# SCH_PCEngineExpansionConnector_2024-10-2.net
KiCad netlist of a schematic drawn in EasyEDA
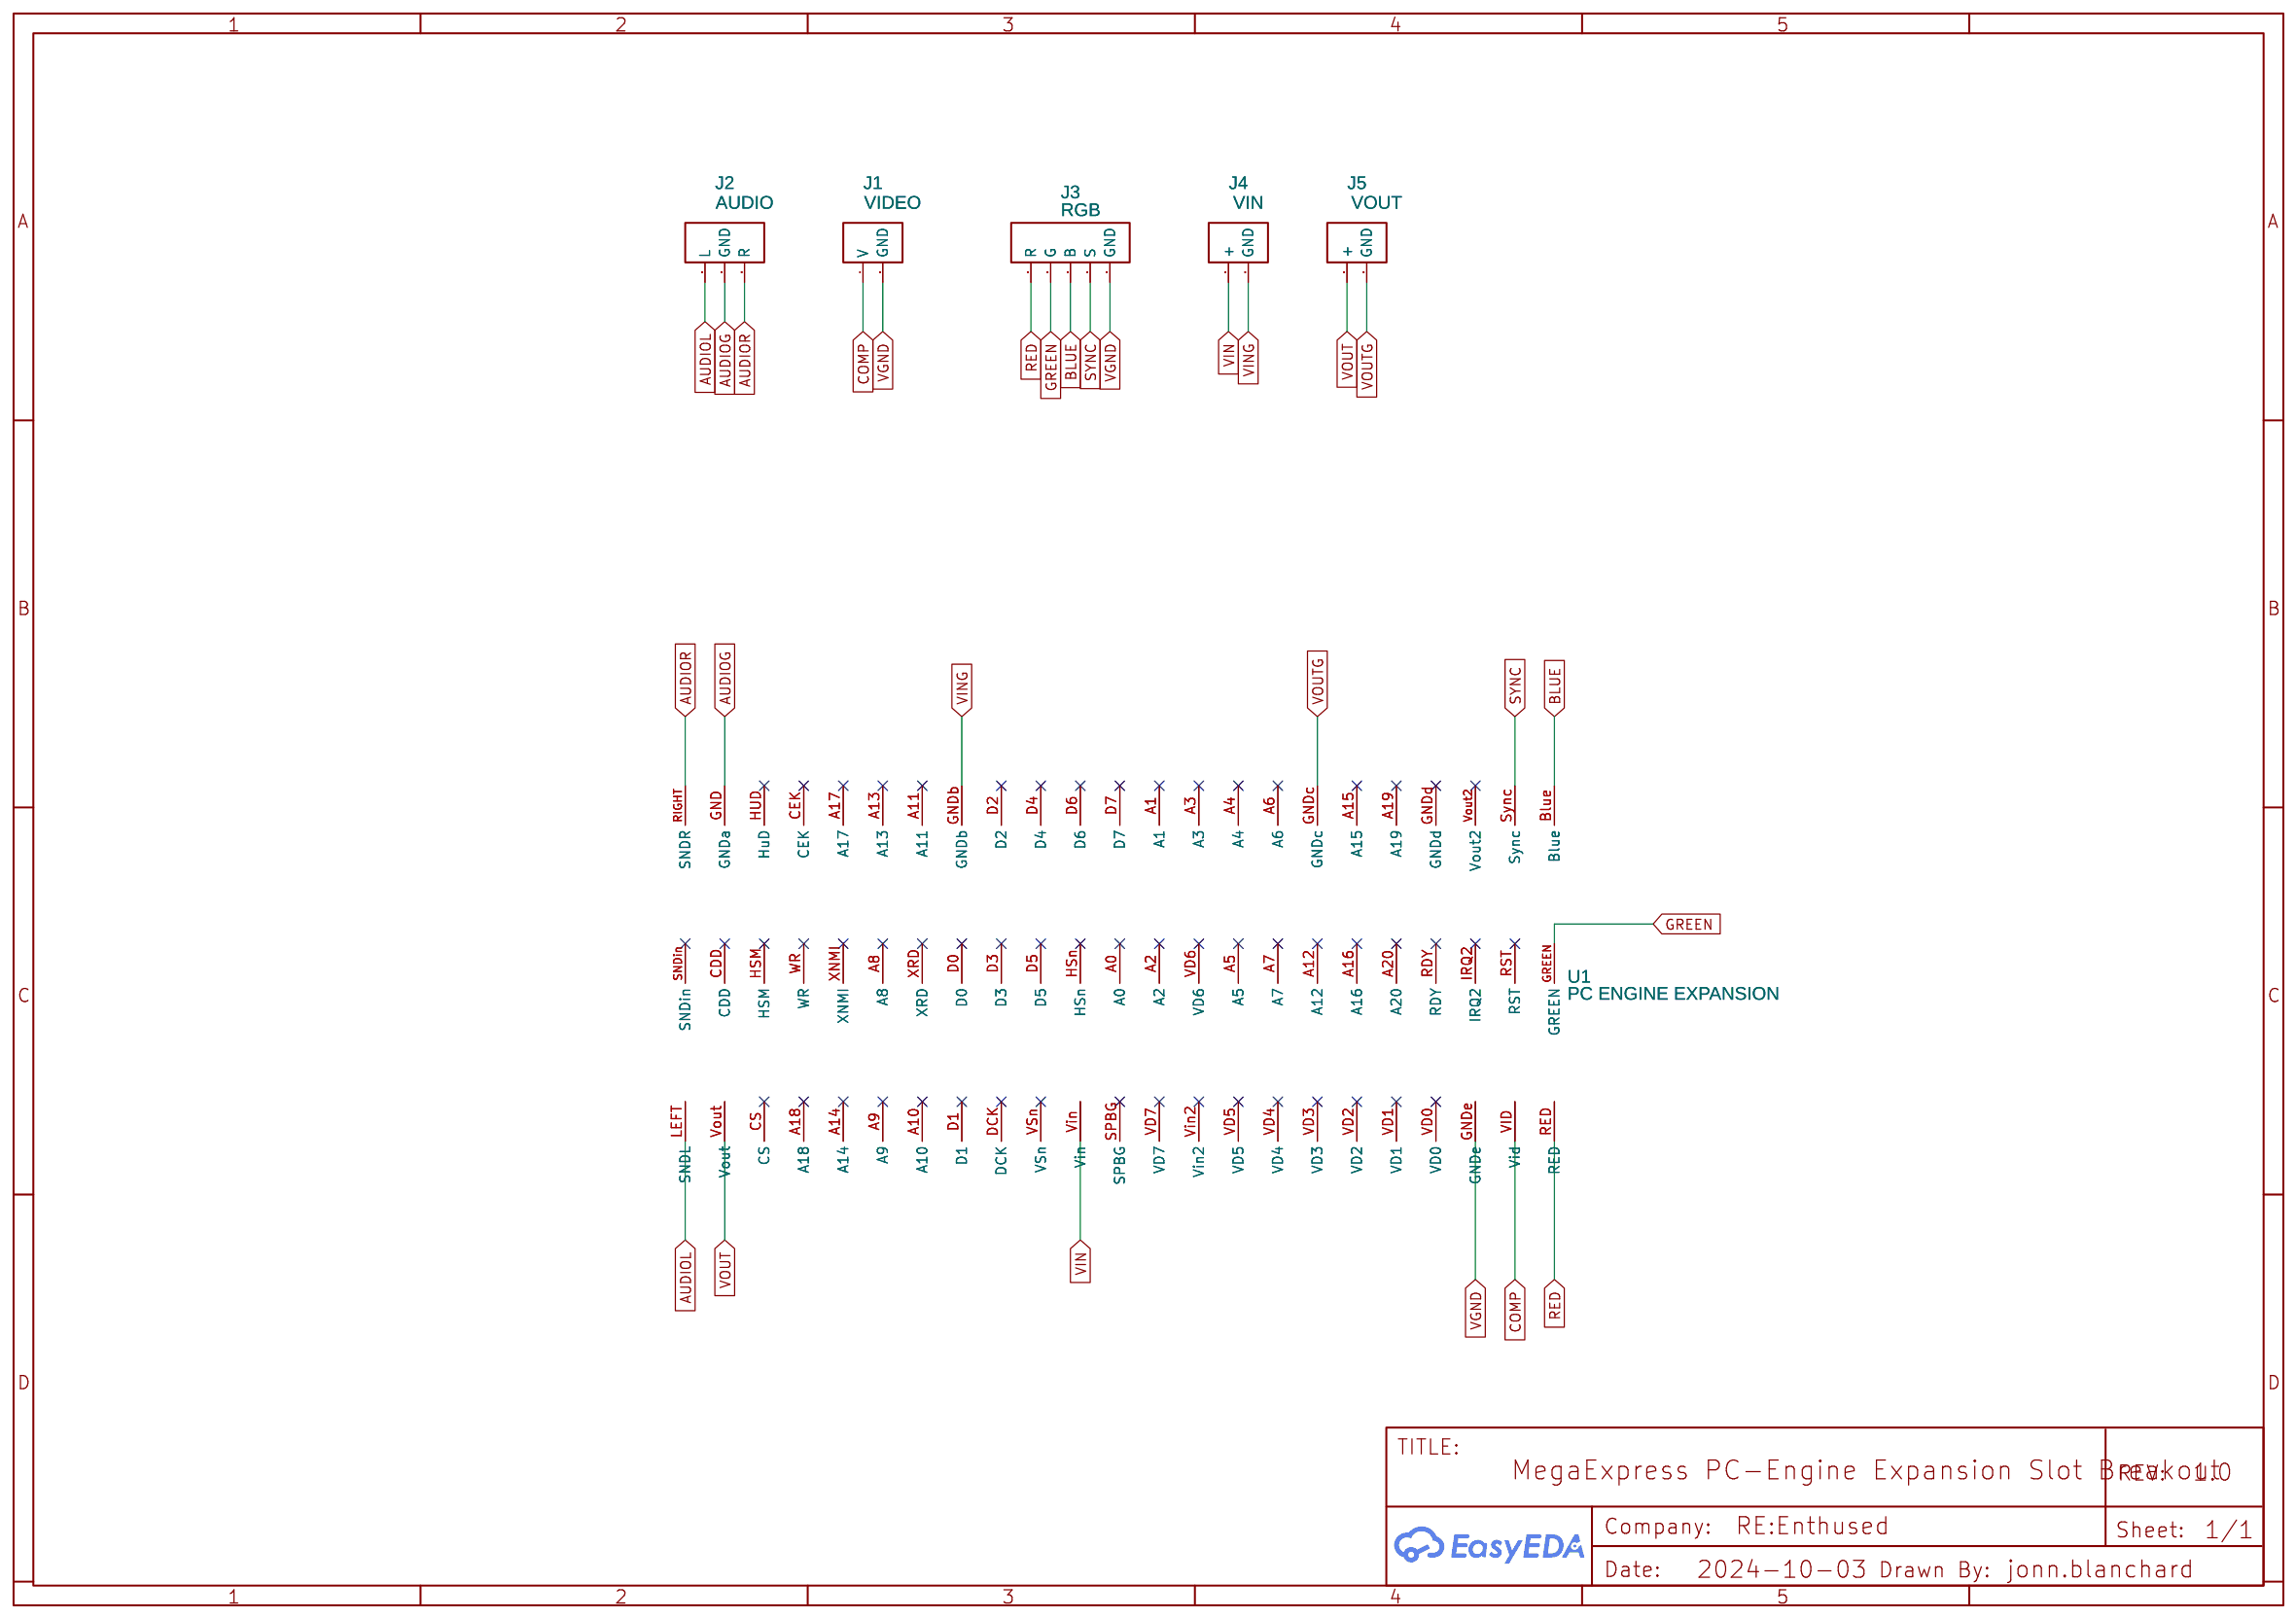
[diagram p0: schematic sheet]

(export (version "E")
  (design (tool "Eeschema 10.0.6"))
  (components
    (comp (ref "J1") (value "VIDEO") (libsource (lib "") (part "HDR-M-2.54_1x2_1")))
    (comp (ref "J2") (value "AUDIO") (libsource (lib "") (part "HDR-M-2.54_1x3")))
    (comp (ref "J3") (value "RGB") (libsource (lib "") (part "HDR-M-2.54_1x5")))
    (comp (ref "J4") (value "VIN") (libsource (lib "") (part "HDR-M-2.54_1x2")))
    (comp (ref "J5") (value "VOUT") (libsource (lib "") (part "HDR-M-2.54_1x2")))
    (comp (ref "U1") (value "PC ENGINE EXPANSION") (libsource (lib "") (part "PC ENGINE EXPANSION")))
  )
  (nets
    (net (code "1") (name "AUDIOG") (class "Default")
      (node (ref "J2") (pin "2") (pinfunction "GND_2") (pintype "input"))
      (node (ref "U1") (pin "GND") (pinfunction "GNDa_GND") (pintype "unspecified"))
    )
    (net (code "2") (name "AUDIOL") (class "Default")
      (node (ref "J2") (pin "1") (pinfunction "L_1") (pintype "input"))
      (node (ref "U1") (pin "LEFT") (pinfunction "SNDL_LEFT") (pintype "unspecified"))
    )
    (net (code "3") (name "AUDIOR") (class "Default")
      (node (ref "J2") (pin "3") (pinfunction "R_3") (pintype "input"))
      (node (ref "U1") (pin "RIGHT") (pinfunction "SNDR_RIGHT") (pintype "unspecified"))
    )
    (net (code "4") (name "BLUE") (class "Default")
      (node (ref "J3") (pin "3") (pinfunction "B_3") (pintype "unspecified"))
      (node (ref "U1") (pin "Blue") (pinfunction "Blue_Blue") (pintype "unspecified"))
    )
    (net (code "5") (name "COMP") (class "Default")
      (node (ref "J1") (pin "1") (pinfunction "V_1") (pintype "unspecified"))
      (node (ref "U1") (pin "VID") (pinfunction "Vid_VID") (pintype "unspecified"))
    )
    (net (code "6") (name "GREEN") (class "Default")
      (node (ref "J3") (pin "2") (pinfunction "G_2") (pintype "unspecified"))
      (node (ref "U1") (pin "GREEN") (pinfunction "GREEN_GREEN") (pintype "unspecified"))
    )
    (net (code "7") (name "RED") (class "Default")
      (node (ref "J3") (pin "1") (pinfunction "R_1") (pintype "unspecified"))
      (node (ref "U1") (pin "RED") (pinfunction "RED_RED") (pintype "unspecified"))
    )
    (net (code "8") (name "SYNC") (class "Default")
      (node (ref "J3") (pin "4") (pinfunction "S_4") (pintype "unspecified"))
      (node (ref "U1") (pin "Sync") (pinfunction "Sync_Sync") (pintype "unspecified"))
    )
    (net (code "9") (name "VGND") (class "Default")
      (node (ref "J1") (pin "2") (pinfunction "GND_2") (pintype "unspecified"))
      (node (ref "J3") (pin "5") (pinfunction "GND_5") (pintype "unspecified"))
      (node (ref "U1") (pin "GNDe") (pinfunction "GNDe_GNDe") (pintype "unspecified"))
    )
    (net (code "10") (name "VIN") (class "Default")
      (node (ref "J4") (pin "1") (pinfunction "+_1") (pintype "unspecified"))
      (node (ref "U1") (pin "Vin") (pinfunction "Vin_Vin") (pintype "unspecified"))
    )
    (net (code "11") (name "VING") (class "Default")
      (node (ref "J4") (pin "2") (pinfunction "GND_2") (pintype "unspecified"))
      (node (ref "U1") (pin "GNDb") (pinfunction "GNDb_GNDb") (pintype "unspecified"))
    )
    (net (code "12") (name "VOUT") (class "Default")
      (node (ref "J5") (pin "1") (pinfunction "+_1") (pintype "unspecified"))
      (node (ref "U1") (pin "Vout") (pinfunction "Vout_Vout") (pintype "unspecified"))
    )
    (net (code "13") (name "VOUTG") (class "Default")
      (node (ref "J5") (pin "2") (pinfunction "GND_2") (pintype "unspecified"))
      (node (ref "U1") (pin "GNDc") (pinfunction "GNDc_GNDc") (pintype "unspecified"))
    )
    (net (code "14") (name "unconnected-(U1-HuD-PadHUD)") (class "Default")
      (node (ref "U1") (pin "HUD") (pinfunction "HuD_HUD") (pintype "unspecified+no_connect"))
    )
    (net (code "15") (name "unconnected-(U1-PadA0)") (class "Default")
      (node (ref "U1") (pin "A0") (pinfunction "A0_A0") (pintype "unspecified+no_connect"))
    )
    (net (code "16") (name "unconnected-(U1-PadA1)") (class "Default")
      (node (ref "U1") (pin "A1") (pinfunction "A1_A1") (pintype "unspecified+no_connect"))
    )
    (net (code "17") (name "unconnected-(U1-PadA2)") (class "Default")
      (node (ref "U1") (pin "A2") (pinfunction "A2_A2") (pintype "unspecified+no_connect"))
    )
    (net (code "18") (name "unconnected-(U1-PadA3)") (class "Default")
      (node (ref "U1") (pin "A3") (pinfunction "A3_A3") (pintype "unspecified+no_connect"))
    )
    (net (code "19") (name "unconnected-(U1-PadA4)") (class "Default")
      (node (ref "U1") (pin "A4") (pinfunction "A4_A4") (pintype "unspecified+no_connect"))
    )
    (net (code "20") (name "unconnected-(U1-PadA5)") (class "Default")
      (node (ref "U1") (pin "A5") (pinfunction "A5_A5") (pintype "unspecified+no_connect"))
    )
    (net (code "21") (name "unconnected-(U1-PadA6)") (class "Default")
      (node (ref "U1") (pin "A6") (pinfunction "A6_A6") (pintype "unspecified+no_connect"))
    )
    (net (code "22") (name "unconnected-(U1-PadA7)") (class "Default")
      (node (ref "U1") (pin "A7") (pinfunction "A7_A7") (pintype "unspecified+no_connect"))
    )
    (net (code "23") (name "unconnected-(U1-PadA8)") (class "Default")
      (node (ref "U1") (pin "A8") (pinfunction "A8_A8") (pintype "unspecified+no_connect"))
    )
    (net (code "24") (name "unconnected-(U1-PadA9)") (class "Default")
      (node (ref "U1") (pin "A9") (pinfunction "A9_A9") (pintype "unspecified+no_connect"))
    )
    (net (code "25") (name "unconnected-(U1-PadA10)") (class "Default")
      (node (ref "U1") (pin "A10") (pinfunction "A10_A10") (pintype "unspecified+no_connect"))
    )
    (net (code "26") (name "unconnected-(U1-PadA11)") (class "Default")
      (node (ref "U1") (pin "A11") (pinfunction "A11_A11") (pintype "unspecified+no_connect"))
    )
    (net (code "27") (name "unconnected-(U1-PadA12)") (class "Default")
      (node (ref "U1") (pin "A12") (pinfunction "A12_A12") (pintype "unspecified+no_connect"))
    )
    (net (code "28") (name "unconnected-(U1-PadA13)") (class "Default")
      (node (ref "U1") (pin "A13") (pinfunction "A13_A13") (pintype "unspecified+no_connect"))
    )
    (net (code "29") (name "unconnected-(U1-PadA14)") (class "Default")
      (node (ref "U1") (pin "A14") (pinfunction "A14_A14") (pintype "unspecified+no_connect"))
    )
    (net (code "30") (name "unconnected-(U1-PadA15)") (class "Default")
      (node (ref "U1") (pin "A15") (pinfunction "A15_A15") (pintype "unspecified+no_connect"))
    )
    (net (code "31") (name "unconnected-(U1-PadA16)") (class "Default")
      (node (ref "U1") (pin "A16") (pinfunction "A16_A16") (pintype "unspecified+no_connect"))
    )
    (net (code "32") (name "unconnected-(U1-PadA17)") (class "Default")
      (node (ref "U1") (pin "A17") (pinfunction "A17_A17") (pintype "unspecified+no_connect"))
    )
    (net (code "33") (name "unconnected-(U1-PadA18)") (class "Default")
      (node (ref "U1") (pin "A18") (pinfunction "A18_A18") (pintype "unspecified+no_connect"))
    )
    (net (code "34") (name "unconnected-(U1-PadA19)") (class "Default")
      (node (ref "U1") (pin "A19") (pinfunction "A19_A19") (pintype "unspecified+no_connect"))
    )
    (net (code "35") (name "unconnected-(U1-PadA20)") (class "Default")
      (node (ref "U1") (pin "A20") (pinfunction "A20_A20") (pintype "unspecified+no_connect"))
    )
    (net (code "36") (name "unconnected-(U1-PadCDD)") (class "Default")
      (node (ref "U1") (pin "CDD") (pinfunction "CDD_CDD") (pintype "unspecified+no_connect"))
    )
    (net (code "37") (name "unconnected-(U1-PadCEK)") (class "Default")
      (node (ref "U1") (pin "CEK") (pinfunction "CEK_CEK") (pintype "unspecified+no_connect"))
    )
    (net (code "38") (name "unconnected-(U1-PadCS)") (class "Default")
      (node (ref "U1") (pin "CS") (pinfunction "CS_CS") (pintype "unspecified+no_connect"))
    )
    (net (code "39") (name "unconnected-(U1-PadD0)") (class "Default")
      (node (ref "U1") (pin "D0") (pinfunction "D0_D0") (pintype "unspecified+no_connect"))
    )
    (net (code "40") (name "unconnected-(U1-PadD1)") (class "Default")
      (node (ref "U1") (pin "D1") (pinfunction "D1_D1") (pintype "unspecified+no_connect"))
    )
    (net (code "41") (name "unconnected-(U1-PadD2)") (class "Default")
      (node (ref "U1") (pin "D2") (pinfunction "D2_D2") (pintype "unspecified+no_connect"))
    )
    (net (code "42") (name "unconnected-(U1-PadD3)") (class "Default")
      (node (ref "U1") (pin "D3") (pinfunction "D3_D3") (pintype "unspecified+no_connect"))
    )
    (net (code "43") (name "unconnected-(U1-PadD4)") (class "Default")
      (node (ref "U1") (pin "D4") (pinfunction "D4_D4") (pintype "unspecified+no_connect"))
    )
    (net (code "44") (name "unconnected-(U1-PadD5)") (class "Default")
      (node (ref "U1") (pin "D5") (pinfunction "D5_D5") (pintype "unspecified+no_connect"))
    )
    (net (code "45") (name "unconnected-(U1-PadD6)") (class "Default")
      (node (ref "U1") (pin "D6") (pinfunction "D6_D6") (pintype "unspecified+no_connect"))
    )
    (net (code "46") (name "unconnected-(U1-PadD7)") (class "Default")
      (node (ref "U1") (pin "D7") (pinfunction "D7_D7") (pintype "unspecified+no_connect"))
    )
    (net (code "47") (name "unconnected-(U1-PadDCK)") (class "Default")
      (node (ref "U1") (pin "DCK") (pinfunction "DCK_DCK") (pintype "unspecified+no_connect"))
    )
    (net (code "48") (name "unconnected-(U1-PadGNDd)") (class "Default")
      (node (ref "U1") (pin "GNDd") (pinfunction "GNDd_GNDd") (pintype "unspecified+no_connect"))
    )
    (net (code "49") (name "unconnected-(U1-PadHSM)") (class "Default")
      (node (ref "U1") (pin "HSM") (pinfunction "HSM_HSM") (pintype "unspecified+no_connect"))
    )
    (net (code "50") (name "unconnected-(U1-PadHSn)") (class "Default")
      (node (ref "U1") (pin "HSn") (pinfunction "HSn_HSn") (pintype "unspecified+no_connect"))
    )
    (net (code "51") (name "unconnected-(U1-PadIRQ2)") (class "Default")
      (node (ref "U1") (pin "IRQ2") (pinfunction "IRQ2_IRQ2") (pintype "unspecified+no_connect"))
    )
    (net (code "52") (name "unconnected-(U1-PadRDY)") (class "Default")
      (node (ref "U1") (pin "RDY") (pinfunction "RDY_RDY") (pintype "unspecified+no_connect"))
    )
    (net (code "53") (name "unconnected-(U1-PadRST)") (class "Default")
      (node (ref "U1") (pin "RST") (pinfunction "RST_RST") (pintype "unspecified+no_connect"))
    )
    (net (code "54") (name "unconnected-(U1-PadSNDin)") (class "Default")
      (node (ref "U1") (pin "SNDin") (pinfunction "SNDin_SNDin") (pintype "unspecified+no_connect"))
    )
    (net (code "55") (name "unconnected-(U1-PadSPBG)") (class "Default")
      (node (ref "U1") (pin "SPBG") (pinfunction "SPBG_SPBG") (pintype "unspecified+no_connect"))
    )
    (net (code "56") (name "unconnected-(U1-PadVD0)") (class "Default")
      (node (ref "U1") (pin "VD0") (pinfunction "VD0_VD0") (pintype "unspecified+no_connect"))
    )
    (net (code "57") (name "unconnected-(U1-PadVD1)") (class "Default")
      (node (ref "U1") (pin "VD1") (pinfunction "VD1_VD1") (pintype "unspecified+no_connect"))
    )
    (net (code "58") (name "unconnected-(U1-PadVD2)") (class "Default")
      (node (ref "U1") (pin "VD2") (pinfunction "VD2_VD2") (pintype "unspecified+no_connect"))
    )
    (net (code "59") (name "unconnected-(U1-PadVD3)") (class "Default")
      (node (ref "U1") (pin "VD3") (pinfunction "VD3_VD3") (pintype "unspecified+no_connect"))
    )
    (net (code "60") (name "unconnected-(U1-PadVD4)") (class "Default")
      (node (ref "U1") (pin "VD4") (pinfunction "VD4_VD4") (pintype "unspecified+no_connect"))
    )
    (net (code "61") (name "unconnected-(U1-PadVD5)") (class "Default")
      (node (ref "U1") (pin "VD5") (pinfunction "VD5_VD5") (pintype "unspecified+no_connect"))
    )
    (net (code "62") (name "unconnected-(U1-PadVD6)") (class "Default")
      (node (ref "U1") (pin "VD6") (pinfunction "VD6_VD6") (pintype "unspecified+no_connect"))
    )
    (net (code "63") (name "unconnected-(U1-PadVD7)") (class "Default")
      (node (ref "U1") (pin "VD7") (pinfunction "VD7_VD7") (pintype "unspecified+no_connect"))
    )
    (net (code "64") (name "unconnected-(U1-PadVSn)") (class "Default")
      (node (ref "U1") (pin "VSn") (pinfunction "VSn_VSn") (pintype "unspecified+no_connect"))
    )
    (net (code "65") (name "unconnected-(U1-PadVin2)") (class "Default")
      (node (ref "U1") (pin "Vin2") (pinfunction "Vin2_Vin2") (pintype "unspecified+no_connect"))
    )
    (net (code "66") (name "unconnected-(U1-PadVout2)") (class "Default")
      (node (ref "U1") (pin "Vout2") (pinfunction "Vout2_Vout2") (pintype "unspecified+no_connect"))
    )
    (net (code "67") (name "unconnected-(U1-PadWR)") (class "Default")
      (node (ref "U1") (pin "WR") (pinfunction "WR_WR") (pintype "unspecified+no_connect"))
    )
    (net (code "68") (name "unconnected-(U1-PadXNMI)") (class "Default")
      (node (ref "U1") (pin "XNMI") (pinfunction "XNMI_XNMI") (pintype "unspecified+no_connect"))
    )
    (net (code "69") (name "unconnected-(U1-PadXRD)") (class "Default")
      (node (ref "U1") (pin "XRD") (pinfunction "XRD_XRD") (pintype "unspecified+no_connect"))
    )
  )
)
